# 3-Sim_Card.net
KiCad netlist of a schematic drawn in Altium Designer
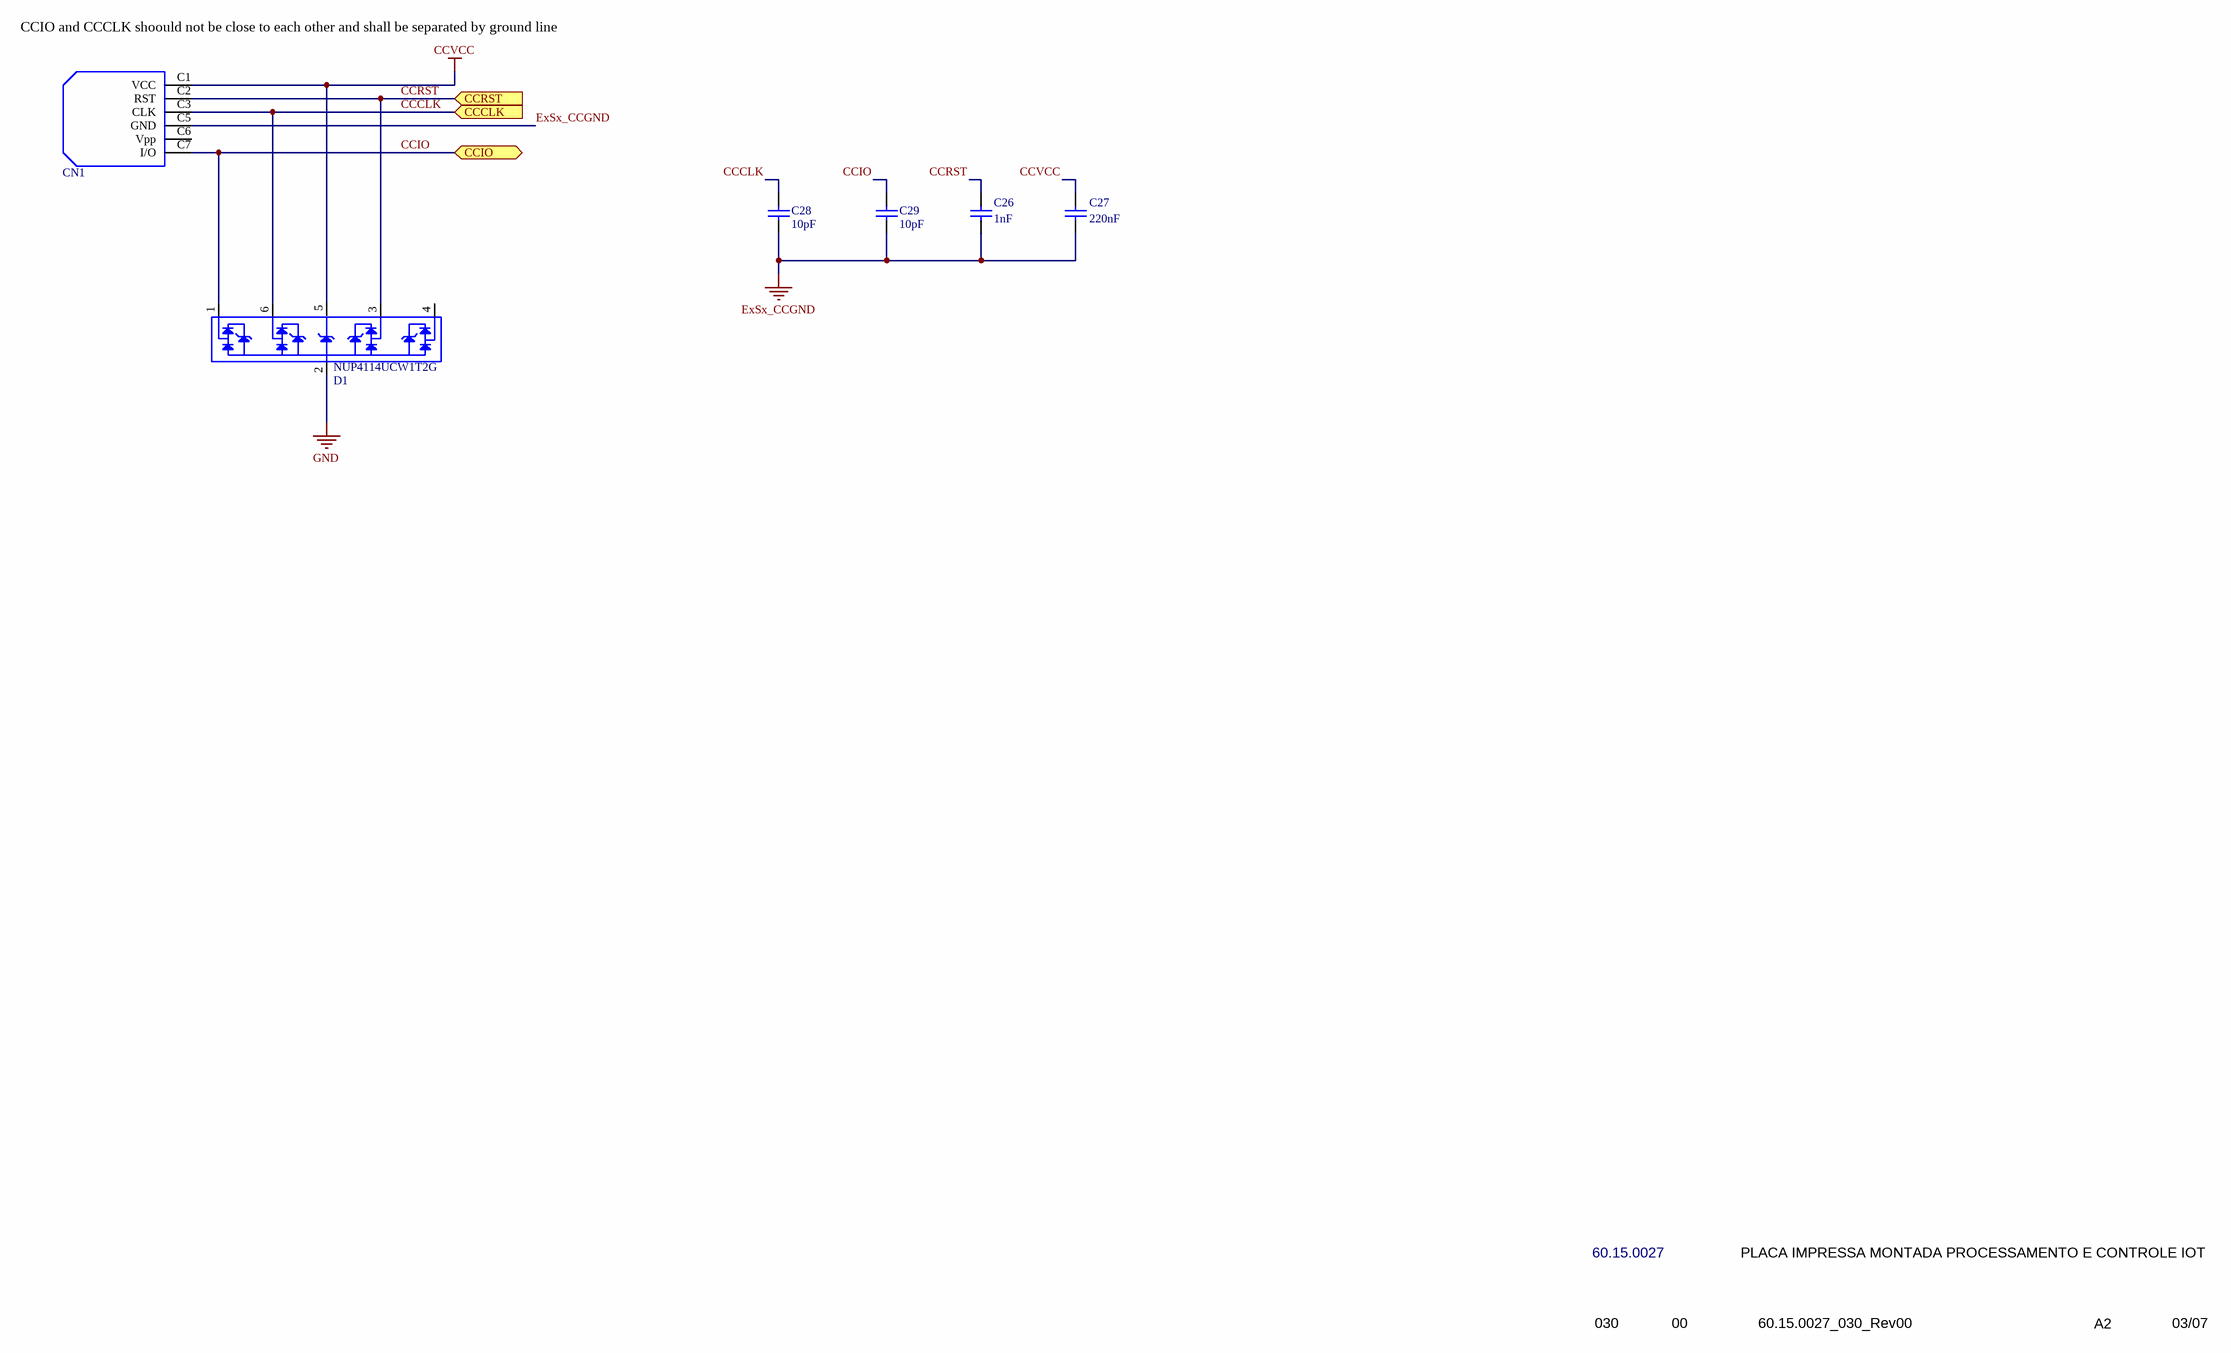
[diagram p0: 3-Sim Card.SchDoc]

(export (version "E")
  (design (tool "Eeschema 10.0.6"))
  (components
    (comp (ref "C26")
      (value "16.23.0800")
      (footprint "16.23.0800")
      (description "CAPACITOR CERAMICO 1nF 25V 5% X7R SMD 0201")
      (fields (field (name "ALTIUM_UNNAMED_1") "1nF"))
      (libsource (lib "OMNI-CAPACITORES") (part "16.23.0800"))
    )
    (comp (ref "C27")
      (value "16.23.0801")
      (footprint "16.23.0801")
      (description "CAPACITOR CERAMICO 220nF 16V 10% X5R SMD 0201")
      (fields (field (name "ALTIUM_UNNAMED_1") "220nF"))
      (libsource (lib "OMNI-CAPACITORES") (part "16.23.0801"))
    )
    (comp (ref "C28")
      (value "16.23.0799")
      (footprint "16.23.0799")
      (description "CAPACITOR CERAMICO 10pF 25V 5% C0G SMD 0201")
      (fields (field (name "ALTIUM_UNNAMED_1") "10pF"))
      (libsource (lib "OMNI-CAPACITORES") (part "16.23.0799"))
    )
    (comp (ref "C29")
      (value "16.23.0799")
      (footprint "16.23.0799")
      (description "CAPACITOR CERAMICO 10pF 25V 5% C0G SMD 0201")
      (fields (field (name "ALTIUM_UNNAMED_1") "10pF"))
      (libsource (lib "OMNI-CAPACITORES") (part "16.23.0799"))
    )
    (comp (ref "CN1")
      (value "SIMCARD-6X6")
      (footprint "28.24.0073")
      (description "CONECTOR FM NANO-D 6 VIAS - BRONZE")
      (libsource (lib "OMNI-CONECTORES") (part "28.24.0073"))
    )
    (comp (ref "D1")
      (value "32.27.0043")
      (footprint "32.27.0043")
      (description "DIODO SUPRESSOR 5.5V 10V SC88")
      (fields (field (name "ALTIUM_UNNAMED_1") "NUP4114UCW1T2G"))
      (libsource (lib "OMNI-DIODOS_LED´s_DISPLAYS") (part "32.27.0043"))
    )
  )
  (nets
    (net (code "1") (name "/CCCLK") (class "Default")
      (node (ref "C28") (pin "2") (pinfunction "2_2") (pintype "passive"))
      (node (ref "CN1") (pin "C3") (pinfunction "CLK_C3") (pintype "passive"))
      (node (ref "D1") (pin "6") (pinfunction "6_6") (pintype "passive"))
    )
    (net (code "2") (name "/CCIO") (class "Default")
      (node (ref "C29") (pin "2") (pinfunction "2_2") (pintype "passive"))
      (node (ref "CN1") (pin "C7") (pinfunction "I/O_C7") (pintype "passive"))
      (node (ref "D1") (pin "1") (pinfunction "1_1") (pintype "passive"))
    )
    (net (code "3") (name "/CCRST") (class "Default")
      (node (ref "C26") (pin "2") (pinfunction "2_2") (pintype "passive"))
      (node (ref "CN1") (pin "C2") (pinfunction "RST_C2") (pintype "passive"))
      (node (ref "D1") (pin "3") (pinfunction "3_3") (pintype "passive"))
    )
    (net (code "4") (name "CCVCC") (class "Default")
      (node (ref "C27") (pin "2") (pinfunction "2_2") (pintype "passive"))
      (node (ref "CN1") (pin "C1") (pinfunction "VCC_C1") (pintype "passive"))
      (node (ref "D1") (pin "5") (pinfunction "5_5") (pintype "power_in"))
    )
    (net (code "5") (name "ExSx_CCGND") (class "Default")
      (node (ref "C26") (pin "1") (pinfunction "1_1") (pintype "passive"))
      (node (ref "C27") (pin "1") (pinfunction "1_1") (pintype "passive"))
      (node (ref "C28") (pin "1") (pinfunction "1_1") (pintype "passive"))
      (node (ref "C29") (pin "1") (pinfunction "1_1") (pintype "passive"))
      (node (ref "CN1") (pin "C5") (pinfunction "GND_C5") (pintype "passive"))
    )
    (net (code "6") (name "GND") (class "Default")
      (node (ref "D1") (pin "2") (pinfunction "2_2") (pintype "power_in"))
    )
    (net (code "7") (name "unconnected-(CN1-Vpp-PadC6)") (class "Default")
      (node (ref "CN1") (pin "C6") (pinfunction "Vpp_C6") (pintype "passive"))
    )
    (net (code "8") (name "unconnected-(D1-Pad4)") (class "Default")
      (node (ref "D1") (pin "4") (pinfunction "4_4") (pintype "passive"))
    )
  )
)
